# ProPrj__1_2024-08-31.net
KiCad netlist of a schematic drawn in EasyEDA Pro
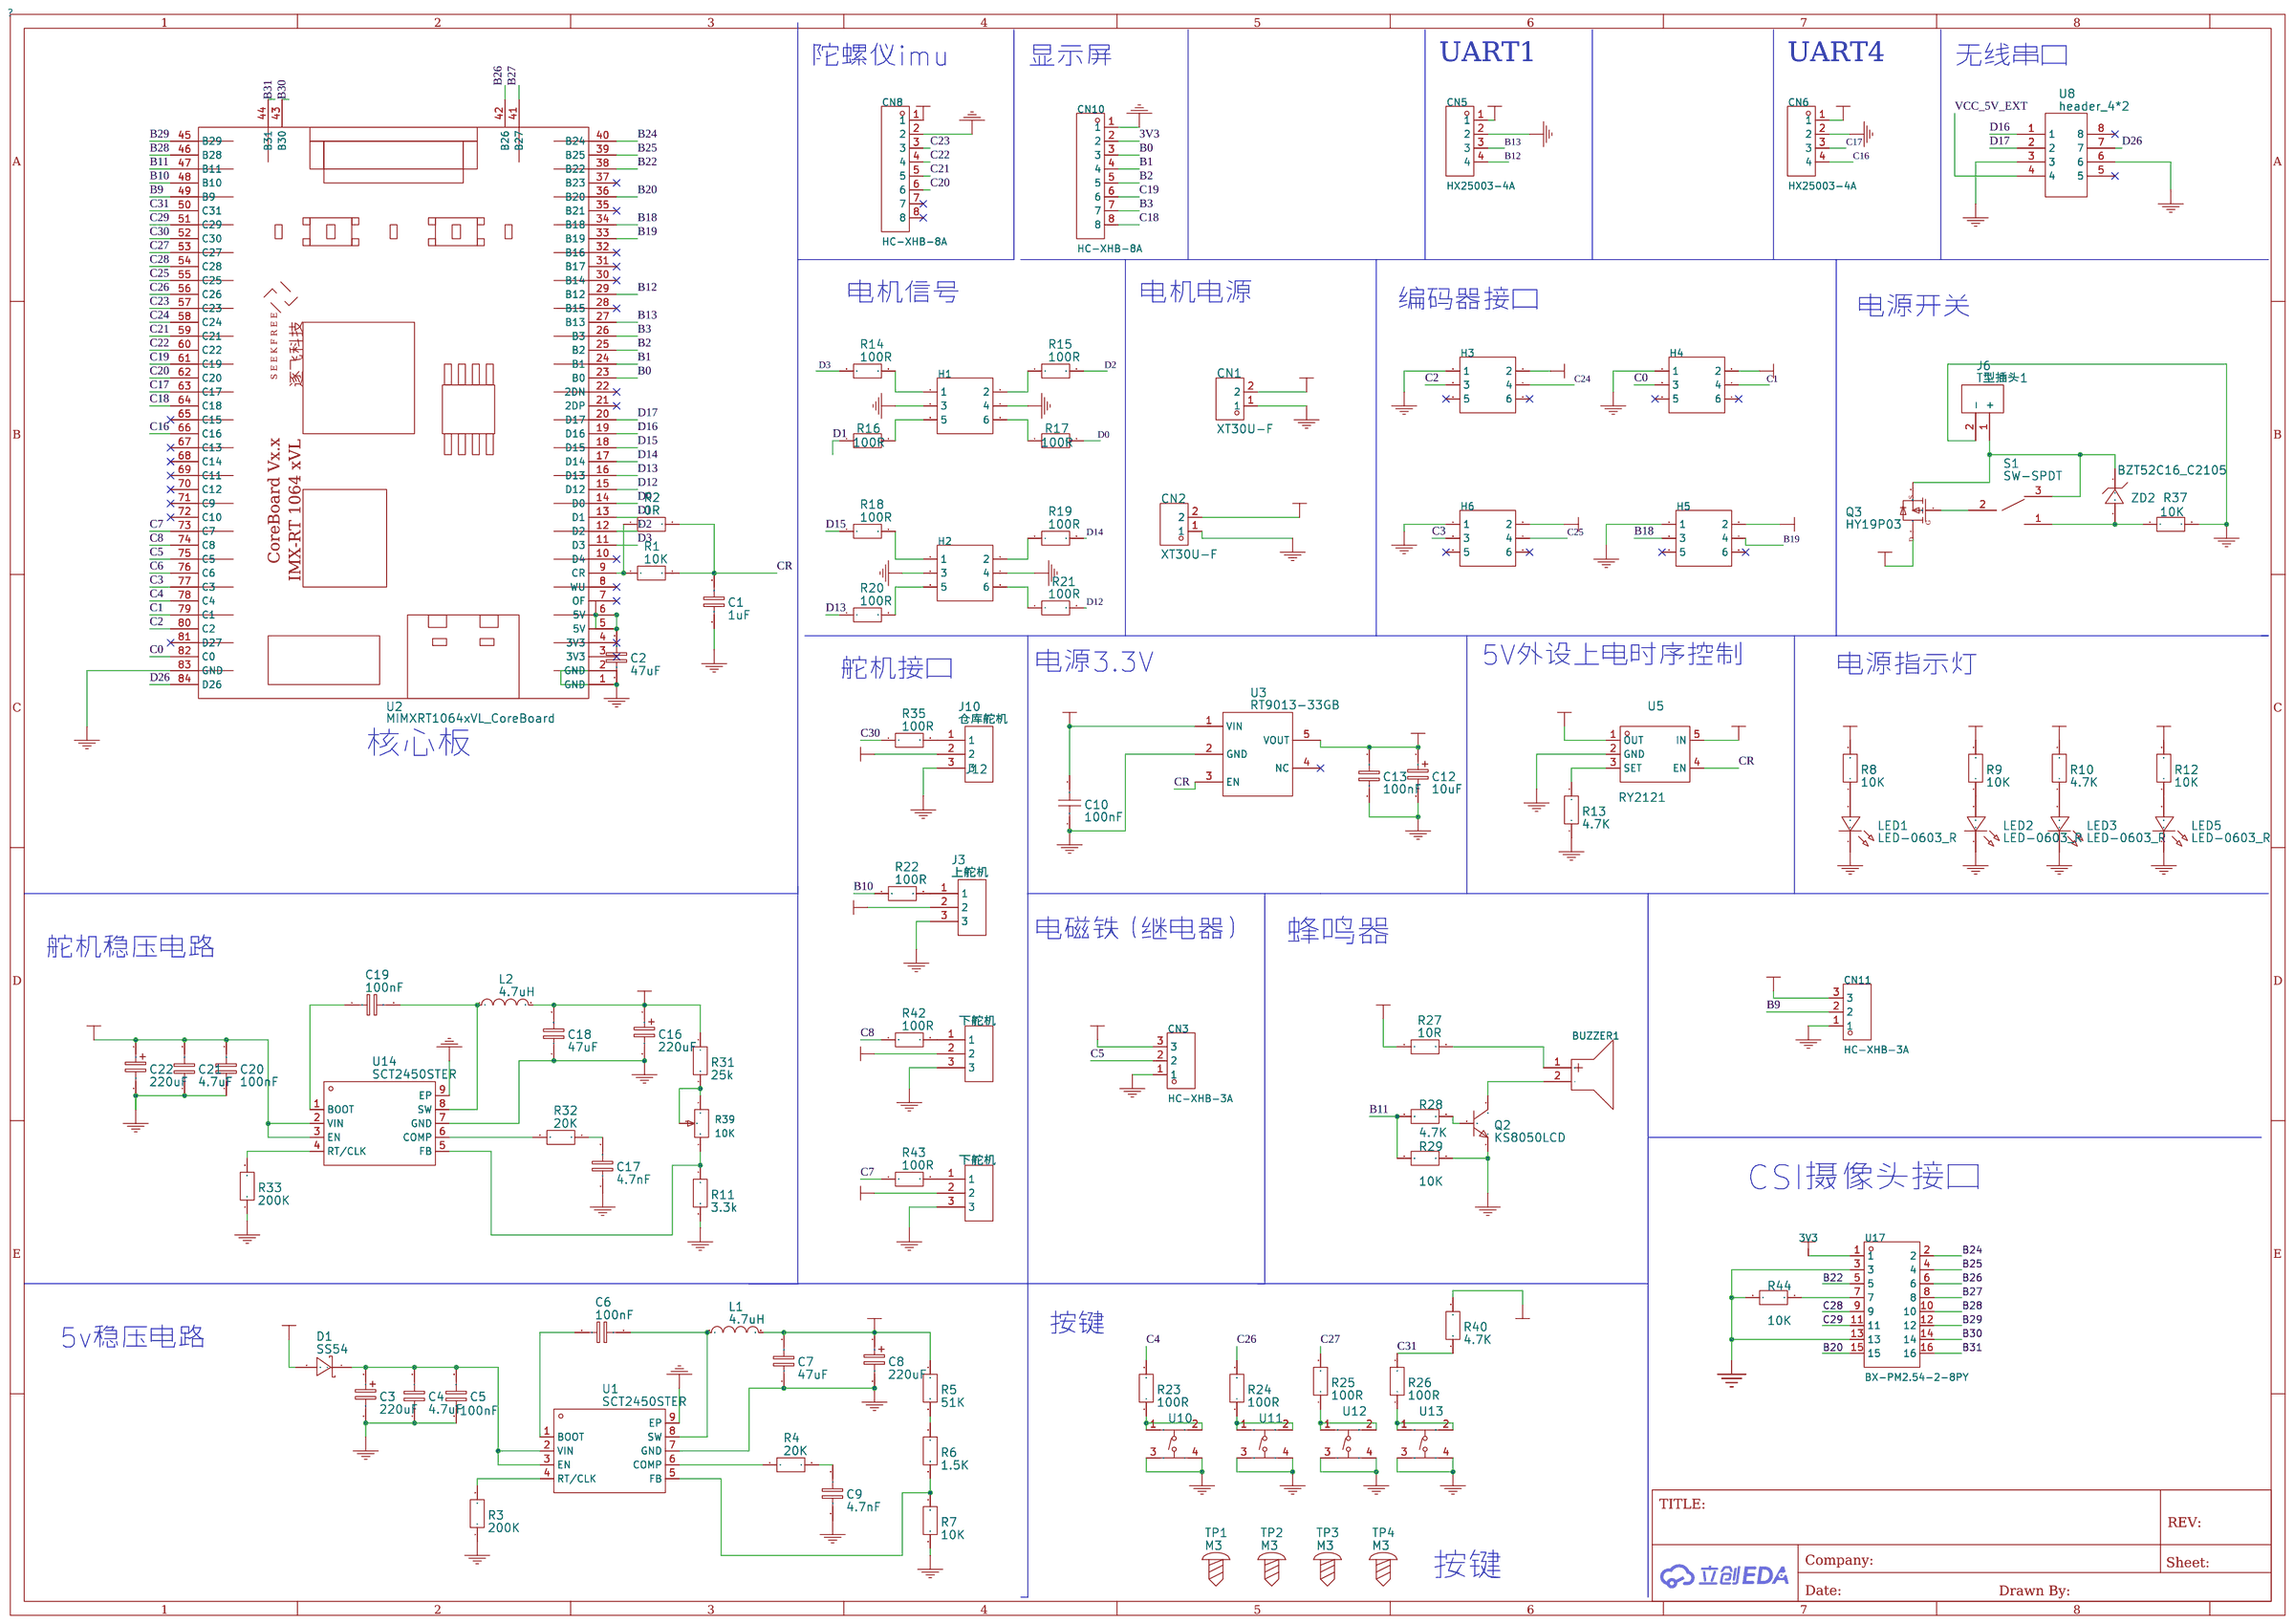
[diagram p0: schematic sheet]

(export (version "E")
  (design (tool "Eeschema 10.0.6"))
  (components
    (comp (ref "BUZZER1")
      (value "有源蜂鸣器直径9*5.5mm3V")
      (footprint "easyedapro:BUZ-TH_BD9.0-P5.00-D0.6-L-FD")
      (libsource (lib "easyedapro") (part "有源蜂鸣器直径9*5.5MM3V"))
    )
    (comp (ref "C1")
      (value "1uF")
      (footprint "easyedapro:C0603")
      (libsource (lib "easyedapro") (part "0.1u"))
    )
    (comp (ref "C2")
      (value "47uF")
      (footprint "easyedapro:C0603")
      (libsource (lib "easyedapro") (part "0.1u"))
    )
    (comp (ref "C3")
      (value "220uF")
      (footprint "easyedapro:贴片铝电解电容6.3*7.7")
      (libsource (lib "easyedapro") (part "220uF"))
    )
    (comp (ref "C4")
      (value "4.7uF")
      (footprint "easyedapro:C0603")
      (libsource (lib "easyedapro") (part "4.7uF"))
    )
    (comp (ref "C5")
      (value "100nF")
      (footprint "easyedapro:C0603")
      (libsource (lib "easyedapro") (part "100nF"))
    )
    (comp (ref "C6")
      (value "100nF")
      (footprint "easyedapro:C0603")
      (libsource (lib "easyedapro") (part "100nF"))
    )
    (comp (ref "C7")
      (value "47uF")
      (footprint "easyedapro:C0603")
      (libsource (lib "easyedapro") (part "47uF"))
    )
    (comp (ref "C8")
      (value "220uF")
      (footprint "easyedapro:贴片铝电解电容6.3*7.7")
      (libsource (lib "easyedapro") (part "220uF"))
    )
    (comp (ref "C9")
      (value "4.7nF")
      (footprint "easyedapro:C0603")
      (libsource (lib "easyedapro") (part "0.1u"))
    )
    (comp (ref "C10") (value "100nF") (footprint "easyedapro:C0603") (libsource (lib "") (part "100nF_1")))
    (comp (ref "C12")
      (value "10uF")
      (footprint "easyedapro:贴片铝电解电容6.3*7.7")
      (libsource (lib "easyedapro") (part "10uF"))
    )
    (comp (ref "C13")
      (value "100nF")
      (footprint "easyedapro:C0603")
      (libsource (lib "easyedapro") (part "100nF"))
    )
    (comp (ref "C16")
      (value "220uF")
      (footprint "easyedapro:贴片铝电解电容6.3*7.7")
      (libsource (lib "easyedapro") (part "220uF"))
    )
    (comp (ref "C17")
      (value "4.7nF")
      (footprint "easyedapro:C0603")
      (libsource (lib "easyedapro") (part "0.1u"))
    )
    (comp (ref "C18")
      (value "47uF")
      (footprint "easyedapro:C0603")
      (libsource (lib "easyedapro") (part "47uF"))
    )
    (comp (ref "C19")
      (value "100nF")
      (footprint "easyedapro:C0603")
      (libsource (lib "easyedapro") (part "100nF"))
    )
    (comp (ref "C20")
      (value "100nF")
      (footprint "easyedapro:C0603")
      (libsource (lib "easyedapro") (part "100nF"))
    )
    (comp (ref "C21")
      (value "4.7uF")
      (footprint "easyedapro:C0603")
      (libsource (lib "easyedapro") (part "4.7uF"))
    )
    (comp (ref "C22")
      (value "220uF")
      (footprint "easyedapro:贴片铝电解电容6.3*7.7")
      (libsource (lib "easyedapro") (part "220uF"))
    )
    (comp (ref "CN1")
      (value "XT30U-F")
      (footprint "easyedapro:CONN-TH_2P-P5.08_DIBO_DB128V-5.08")
      (fields (field (name "Manufacturer") "AMASS(艾迈斯)"))
      (libsource (lib "easyedapro") (part "DB128V-5.08-2P-GN-S"))
    )
    (comp (ref "CN2")
      (value "XT30U-F")
      (footprint "easyedapro:CONN-TH_2P-P5.08_DIBO_DB128V-5.08")
      (fields (field (name "Manufacturer") "AMASS(艾迈斯)"))
      (libsource (lib "easyedapro") (part "DB128V-5.08-2P-GN-S"))
    )
    (comp (ref "CN3")
      (value "HC-XHB-3A")
      (footprint "easyedapro:CONN-TH_3P-P2.50_HC-XHB-3A")
      (description "参考系列:-;间距:2.5mm;插针结构:1x3P;排数:1;每排PIN数:3;行距:-;公母:公型插针;安装方式:直插;额定电流:3A;工作温度范围:-25°C~+85°C;")
      (fields (field (name "Manufacturer") "HCTL(华灿天禄)"))
      (libsource (lib "easyedapro") (part "HC-XHB-3A"))
    )
    (comp (ref "CN5")
      (value "HX25003-4A")
      (footprint "easyedapro:CONN-TH_4P-P2.50_HX25003-4A")
      (description "参考系列:XH;间距:2.5mm;插针结构:1x4P;排数:1;每排PIN数:4;行距:-;公母:公型插针;安装方式:直插;额定电流:-;工作温度范围:-;")
      (fields (field (name "Manufacturer") "HX(红星)"))
      (libsource (lib "easyedapro") (part "HX25003-4A"))
    )
    (comp (ref "CN6")
      (value "HX25003-4A")
      (footprint "easyedapro:CONN-TH_4P-P2.50_HX25003-4A")
      (description "参考系列:XH;间距:2.5mm;插针结构:1x4P;排数:1;每排PIN数:4;行距:-;公母:公型插针;安装方式:直插;额定电流:-;工作温度范围:-;")
      (fields (field (name "Manufacturer") "HX(红星)"))
      (libsource (lib "easyedapro") (part "HX25003-4A"))
    )
    (comp (ref "CN8")
      (value "HC-XHB-8A")
      (footprint "easyedapro:CONN-TH_8P-P2.50_HCTL_HC-XHB-8A")
      (description "参考系列:-;间距:2.5mm;插针结构:1x8P;排数:1;每排PIN数:8;行距:-;公母:公型插针;安装方式:直插;额定电流:3A;工作温度范围:-25°C~+85°C;")
      (fields (field (name "Manufacturer") "HCTL(华灿天禄)"))
      (libsource (lib "easyedapro") (part "HC-XHB-8A"))
    )
    (comp (ref "CN10")
      (value "HC-XHB-8A")
      (footprint "easyedapro:CONN-TH_8P-P2.50_HCTL_HC-XHB-8A")
      (description "参考系列:-;间距:2.5mm;插针结构:1x8P;排数:1;每排PIN数:8;行距:-;公母:公型插针;安装方式:直插;额定电流:3A;工作温度范围:-25°C~+85°C;")
      (fields (field (name "Manufacturer") "HCTL(华灿天禄)"))
      (libsource (lib "easyedapro") (part "HC-XHB-8A"))
    )
    (comp (ref "CN11")
      (value "HC-XHB-3A")
      (footprint "easyedapro:CONN-TH_3P-P2.50_HC-XHB-3A")
      (description "参考系列:-;间距:2.5mm;插针结构:1x3P;排数:1;每排PIN数:3;行距:-;公母:公型插针;安装方式:直插;额定电流:3A;工作温度范围:-25°C~+85°C;")
      (fields (field (name "Manufacturer") "HCTL(华灿天禄)"))
      (libsource (lib "easyedapro") (part "HC-XHB-3A"))
    )
    (comp (ref "D1")
      (value "SS54")
      (footprint "easyedapro:SS54")
      (libsource (lib "easyedapro") (part "SS54"))
    )
    (comp (ref "H1")
      (value "~")
      (footprint "easyedapro:HDR-TH_6P-P2.54-V-F-R2-C3-S2.54")
      (libsource (lib "easyedapro") (part "HDR-F-2.54_2x3"))
    )
    (comp (ref "H2")
      (value "~")
      (footprint "easyedapro:HDR-TH_6P-P2.54-V-F-R2-C3-S2.54")
      (libsource (lib "easyedapro") (part "HDR-F-2.54_2x3"))
    )
    (comp (ref "H3")
      (value "~")
      (footprint "easyedapro:HDR-TH_6P-P2.54-V-F-R2-C3-S2.54")
      (libsource (lib "easyedapro") (part "HDR-F-2.54_2x3"))
    )
    (comp (ref "H4")
      (value "~")
      (footprint "easyedapro:HDR-TH_6P-P2.54-V-F-R2-C3-S2.54")
      (libsource (lib "easyedapro") (part "HDR-F-2.54_2x3"))
    )
    (comp (ref "H5")
      (value "~")
      (footprint "easyedapro:HDR-TH_6P-P2.54-V-F-R2-C3-S2.54")
      (libsource (lib "easyedapro") (part "HDR-F-2.54_2x3"))
    )
    (comp (ref "H6")
      (value "~")
      (footprint "easyedapro:HDR-TH_6P-P2.54-V-F-R2-C3-S2.54")
      (libsource (lib "easyedapro") (part "HDR-F-2.54_2x3"))
    )
    (comp (ref "J3")
      (value "上舵机")
      (footprint "easyedapro:2.54排针1X3")
      (libsource (lib "easyedapro") (part "舵机"))
    )
    (comp (ref "J6")
      (value "T型插头1")
      (footprint "easyedapro:T型插头")
      (libsource (lib "easyedapro") (part "T型插头1"))
    )
    (comp (ref "J10")
      (value "仓库舵机")
      (footprint "easyedapro:2.54排针1X3")
      (libsource (lib "easyedapro") (part "舵机"))
    )
    (comp (ref "J12")
      (value "下舵机")
      (footprint "easyedapro:2.54排针1X3")
      (libsource (lib "easyedapro") (part "舵机"))
    )
    (comp (ref "J13")
      (value "下舵机")
      (footprint "easyedapro:2.54排针1X3")
      (libsource (lib "easyedapro") (part "舵机"))
    )
    (comp (ref "L1")
      (value "4.7uH")
      (footprint "easyedapro:IND-SMD_L6.0-W6.0_SMNR6028")
      (fields
        (field (name "Manufacturer Part") "SMNR6028-680MT")
        (field (name "Manufacturer") "ShunXiang Connaught Elec")
      )
      (libsource (lib "easyedapro") (part "4.7uH"))
    )
    (comp (ref "L2")
      (value "4.7uH")
      (footprint "easyedapro:IND-SMD_L6.0-W6.0_SMNR6028")
      (fields
        (field (name "Manufacturer Part") "SMNR6028-680MT")
        (field (name "Manufacturer") "ShunXiang Connaught Elec")
      )
      (libsource (lib "easyedapro") (part "4.7uH"))
    )
    (comp (ref "LED1")
      (value "LED-0603_R")
      (footprint "easyedapro:LED0603_RED")
      (fields
        (field (name "Manufacturer Part") "19-217/R6C-AL1M2VY/3T")
        (field (name "Manufacturer") "EVERLIGHT(台湾亿光)")
      )
      (libsource (lib "easyedapro") (part "LED-0603_R"))
    )
    (comp (ref "LED2")
      (value "LED-0603_R")
      (footprint "easyedapro:LED0603_RED")
      (fields
        (field (name "Manufacturer Part") "19-217/R6C-AL1M2VY/3T")
        (field (name "Manufacturer") "EVERLIGHT(台湾亿光)")
      )
      (libsource (lib "easyedapro") (part "LED-0603_R"))
    )
    (comp (ref "LED3")
      (value "LED-0603_R")
      (footprint "easyedapro:LED0603_RED")
      (fields
        (field (name "Manufacturer Part") "19-217/R6C-AL1M2VY/3T")
        (field (name "Manufacturer") "EVERLIGHT(台湾亿光)")
      )
      (libsource (lib "easyedapro") (part "LED-0603_R"))
    )
    (comp (ref "LED5")
      (value "LED-0603_R")
      (footprint "easyedapro:LED0603_RED")
      (fields
        (field (name "Manufacturer Part") "19-217/R6C-AL1M2VY/3T")
        (field (name "Manufacturer") "EVERLIGHT(台湾亿光)")
      )
      (libsource (lib "easyedapro") (part "LED-0603_R"))
    )
    (comp (ref "Q2")
      (value "KS8050LCD")
      (footprint "easyedapro:SOT-23-3_L2.9-W1.3-P1.90-LS2.4-BR")
      (fields (field (name "Manufacturer") "Kodenshi AUK"))
      (libsource (lib "easyedapro") (part "KS8050LCD"))
    )
    (comp (ref "Q3")
      (value "HY19P03")
      (footprint "easyedapro:TO-252AA")
      (libsource (lib "easyedapro") (part "HY19P03"))
    )
    (comp (ref "R1") (value "10K") (footprint "easyedapro:R0603") (libsource (lib "easyedapro") (part "10k")))
    (comp (ref "R2") (value "0R") (footprint "easyedapro:R0603") (libsource (lib "easyedapro") (part "0R")))
    (comp (ref "R3")
      (value "200K")
      (footprint "easyedapro:R0603")
      (libsource (lib "easyedapro") (part "200K"))
    )
    (comp (ref "R4") (value "20K") (footprint "easyedapro:R0603") (libsource (lib "easyedapro") (part "1k")))
    (comp (ref "R5") (value "51K") (footprint "easyedapro:R0603") (libsource (lib "easyedapro") (part "51K")))
    (comp (ref "R6")
      (value "1.5K")
      (footprint "easyedapro:R0603")
      (libsource (lib "easyedapro") (part "1.5K"))
    )
    (comp (ref "R7") (value "10K") (footprint "easyedapro:R0603") (libsource (lib "easyedapro") (part "10K")))
    (comp (ref "R8") (value "10K") (footprint "easyedapro:R0603") (libsource (lib "easyedapro") (part "10K")))
    (comp (ref "R9") (value "10K") (footprint "easyedapro:R0603") (libsource (lib "easyedapro") (part "10K")))
    (comp (ref "R10")
      (value "4.7K")
      (footprint "easyedapro:R0603")
      (libsource (lib "easyedapro") (part "10K"))
    )
    (comp (ref "R11")
      (value "3.3k")
      (footprint "easyedapro:R0603")
      (libsource (lib "easyedapro") (part "10K"))
    )
    (comp (ref "R12")
      (value "10K")
      (footprint "easyedapro:R0603")
      (libsource (lib "easyedapro") (part "4.7K"))
    )
    (comp (ref "R13")
      (value "4.7K")
      (footprint "easyedapro:R0603")
      (libsource (lib "easyedapro") (part "4.7K"))
    )
    (comp (ref "R14")
      (value "100R")
      (footprint "easyedapro:R0603")
      (libsource (lib "easyedapro") (part "100R"))
    )
    (comp (ref "R15")
      (value "100R")
      (footprint "easyedapro:R0603")
      (libsource (lib "easyedapro") (part "100R"))
    )
    (comp (ref "R16")
      (value "100R")
      (footprint "easyedapro:R0603")
      (libsource (lib "easyedapro") (part "100R"))
    )
    (comp (ref "R17")
      (value "100R")
      (footprint "easyedapro:R0603")
      (libsource (lib "easyedapro") (part "100R"))
    )
    (comp (ref "R18")
      (value "100R")
      (footprint "easyedapro:R0603")
      (libsource (lib "easyedapro") (part "100R"))
    )
    (comp (ref "R19")
      (value "100R")
      (footprint "easyedapro:R0603")
      (libsource (lib "easyedapro") (part "100R"))
    )
    (comp (ref "R20")
      (value "100R")
      (footprint "easyedapro:R0603")
      (libsource (lib "easyedapro") (part "100R"))
    )
    (comp (ref "R21")
      (value "100R")
      (footprint "easyedapro:R0603")
      (libsource (lib "easyedapro") (part "100R"))
    )
    (comp (ref "R22")
      (value "100R")
      (footprint "easyedapro:R0603")
      (libsource (lib "easyedapro") (part "1k"))
    )
    (comp (ref "R23")
      (value "100R")
      (footprint "easyedapro:R0603")
      (libsource (lib "easyedapro") (part "100R"))
    )
    (comp (ref "R24")
      (value "100R")
      (footprint "easyedapro:R0603")
      (libsource (lib "easyedapro") (part "100R"))
    )
    (comp (ref "R25")
      (value "100R")
      (footprint "easyedapro:R0603")
      (libsource (lib "easyedapro") (part "100R"))
    )
    (comp (ref "R26")
      (value "100R")
      (footprint "easyedapro:R0603")
      (libsource (lib "easyedapro") (part "100R"))
    )
    (comp (ref "R27") (value "10R") (footprint "easyedapro:R0603") (libsource (lib "easyedapro") (part "1k")))
    (comp (ref "R28")
      (value "4.7K")
      (footprint "easyedapro:R0603")
      (libsource (lib "easyedapro") (part "1k"))
    )
    (comp (ref "R29") (value "10K") (footprint "easyedapro:R0603") (libsource (lib "easyedapro") (part "1k")))
    (comp (ref "R31")
      (value "25k")
      (footprint "easyedapro:R0603")
      (libsource (lib "easyedapro") (part "51K"))
    )
    (comp (ref "R32") (value "20K") (footprint "easyedapro:R0603") (libsource (lib "easyedapro") (part "1k")))
    (comp (ref "R33")
      (value "200K")
      (footprint "easyedapro:R0603")
      (libsource (lib "easyedapro") (part "200K"))
    )
    (comp (ref "R35")
      (value "100R")
      (footprint "easyedapro:R0603")
      (libsource (lib "easyedapro") (part "1k"))
    )
    (comp (ref "R37")
      (value "10K")
      (footprint "easyedapro:R0603")
      (libsource (lib "easyedapro") (part "10K"))
    )
    (comp (ref "R39")
      (value "10K")
      (footprint "easyedapro:RES-ADJ-TH_3296W")
      (description "阻值:10kΩ;精度:±10%;")
      (fields (field (name "Manufacturer Part") "3296W-1-103LF") (field (name "Manufacturer") "BOURNS"))
      (libsource (lib "easyedapro") (part "3296W-1-103LF"))
    )
    (comp (ref "R40")
      (value "4.7K")
      (footprint "easyedapro:R0603")
      (libsource (lib "easyedapro") (part "100R"))
    )
    (comp (ref "R42")
      (value "100R")
      (footprint "easyedapro:R0603")
      (libsource (lib "easyedapro") (part "1k"))
    )
    (comp (ref "R43")
      (value "100R")
      (footprint "easyedapro:R0603")
      (libsource (lib "easyedapro") (part "1k"))
    )
    (comp (ref "R44") (value "10K") (footprint "easyedapro:R0603") (libsource (lib "easyedapro") (part "1k")))
    (comp (ref "S1")
      (value "SW-SPDT")
      (footprint "easyedapro:SS12D10")
      (fields (field (name "Publisher") "Altium Limited"))
      (libsource (lib "easyedapro") (part "SW-SPDT"))
    )
    (comp (ref "TP1") (value "M3") (footprint "easyedapro:M3") (libsource (lib "easyedapro") (part "M3")))
    (comp (ref "TP2") (value "M3") (footprint "easyedapro:M3") (libsource (lib "easyedapro") (part "M3")))
    (comp (ref "TP3") (value "M3") (footprint "easyedapro:M3") (libsource (lib "easyedapro") (part "M3")))
    (comp (ref "TP4") (value "M3") (footprint "easyedapro:M3") (libsource (lib "easyedapro") (part "M3")))
    (comp (ref "U1")
      (value "SCT2450STER")
      (footprint "easyedapro:ESOP-8_L4.9-W3.9-P1.27-LS6.0-BL-EP")
      (fields (field (name "Manufacturer") "SCT"))
      (libsource (lib "easyedapro") (part "SCT2450STER"))
    )
    (comp (ref "U2")
      (value "MIMXRT1064xVL_CoreBoard")
      (footprint "easyedapro:MIMXRT1064XVL_COREBOARD")
      (libsource (lib "easyedapro") (part "MIMXRT1064xVL_CoreBoard"))
    )
    (comp (ref "U3")
      (value "RT9013-33GB")
      (footprint "easyedapro:SOT-23-5_L3.0-W1.7-P0.95-LS2.8-BR")
      (fields (field (name "Manufacturer") "RICHTEK"))
      (libsource (lib "easyedapro") (part "RT9013-33GB"))
    )
    (comp (ref "U5")
      (value "RY2121")
      (footprint "easyedapro:SOT-23-5_L3.0-W1.6-P0.95-LS2.8-BL")
      (fields (field (name "Manufacturer") "RYCHiP(蕊源)"))
      (libsource (lib "easyedapro") (part "RY2121"))
    )
    (comp (ref "U8")
      (value "header_4*2")
      (footprint "easyedapro:HEADER_4*2")
      (libsource (lib "easyedapro") (part "header_4*2"))
    )
    (comp (ref "U10")
      (value "贴片按键4*4*3.5M")
      (footprint "easyedapro:KEY-SMD_4P-L5.1-W5.1-P3.70-LS6.5")
      (fields (field (name "Manufacturer Part") "贴片按键4*4*3.5m"))
      (libsource (lib "easyedapro") (part "贴片按键4*4*3.5M"))
    )
    (comp (ref "U11")
      (value "贴片按键4*4*3.5M")
      (footprint "easyedapro:KEY-SMD_4P-L5.1-W5.1-P3.70-LS6.5")
      (fields (field (name "Manufacturer Part") "贴片按键4*4*3.5m"))
      (libsource (lib "easyedapro") (part "贴片按键4*4*3.5M"))
    )
    (comp (ref "U12")
      (value "贴片按键4*4*3.5M")
      (footprint "easyedapro:KEY-SMD_4P-L5.1-W5.1-P3.70-LS6.5")
      (fields (field (name "Manufacturer Part") "贴片按键4*4*3.5m"))
      (libsource (lib "easyedapro") (part "贴片按键4*4*3.5M"))
    )
    (comp (ref "U13")
      (value "贴片按键4*4*3.5M")
      (footprint "easyedapro:KEY-SMD_4P-L5.1-W5.1-P3.70-LS6.5")
      (fields (field (name "Manufacturer Part") "贴片按键4*4*3.5m"))
      (libsource (lib "easyedapro") (part "贴片按键4*4*3.5M"))
    )
    (comp (ref "U14")
      (value "SCT2450STER")
      (footprint "easyedapro:ESOP-8_L4.9-W3.9-P1.27-LS6.0-BL-EP")
      (fields (field (name "Manufacturer") "SCT"))
      (libsource (lib "easyedapro") (part "SCT2450STER"))
    )
    (comp (ref "U17")
      (value "BX-PM2.54-2-8PY")
      (footprint "easyedapro:HDR-TH_16P-P2.54-V-F-R2-C8-S2.54-1")
      (fields (field (name "Manufacturer") "Bossie(博锡)"))
      (libsource (lib "easyedapro") (part "BX-PM2.54-2-8PY"))
    )
    (comp (ref "ZD2")
      (value "BZT52C16_C2105")
      (footprint "easyedapro:SOD-123_L2.8-W1.8-LS3.7-RD")
      (fields (field (name "Manufacturer Part") "BZT52C16") (field (name "Manufacturer") "CJ"))
      (libsource (lib "easyedapro") (part "BZT52C16_C2105"))
    )
  )
  (nets
    (net (code "1") (name "/B0") (class "Default")
      (node (ref "CN10") (pin "3") (pinfunction "3_3") (pintype "input"))
      (node (ref "U2") (pin "23") (pinfunction "B0_23") (pintype "input"))
    )
    (net (code "2") (name "/B1") (class "Default")
      (node (ref "CN10") (pin "4") (pinfunction "4_4") (pintype "input"))
      (node (ref "U2") (pin "24") (pinfunction "B1_24") (pintype "input"))
    )
    (net (code "3") (name "/B2") (class "Default")
      (node (ref "CN10") (pin "5") (pinfunction "5_5") (pintype "input"))
      (node (ref "U2") (pin "25") (pinfunction "B2_25") (pintype "input"))
    )
    (net (code "4") (name "/B3") (class "Default")
      (node (ref "CN10") (pin "7") (pinfunction "7_7") (pintype "input"))
      (node (ref "U2") (pin "26") (pinfunction "B3_26") (pintype "input"))
    )
    (net (code "5") (name "/B9") (class "Default")
      (node (ref "CN11") (pin "2") (pinfunction "2_2") (pintype "input"))
      (node (ref "U2") (pin "49") (pinfunction "B9_49") (pintype "input"))
    )
    (net (code "6") (name "/B10") (class "Default")
      (node (ref "R22") (pin "1") (pinfunction "1_1") (pintype "input"))
      (node (ref "U2") (pin "48") (pinfunction "B10_48") (pintype "input"))
    )
    (net (code "7") (name "/B11") (class "Default")
      (node (ref "R28") (pin "1") (pinfunction "1_1") (pintype "input"))
      (node (ref "R29") (pin "1") (pinfunction "1_1") (pintype "input"))
      (node (ref "U2") (pin "47") (pinfunction "B11_47") (pintype "input"))
    )
    (net (code "8") (name "/B12") (class "Default")
      (node (ref "CN5") (pin "4") (pinfunction "4_4") (pintype "input"))
      (node (ref "U2") (pin "29") (pinfunction "B12_29") (pintype "input"))
    )
    (net (code "9") (name "/B13") (class "Default")
      (node (ref "CN5") (pin "3") (pinfunction "3_3") (pintype "input"))
      (node (ref "U2") (pin "27") (pinfunction "B13_27") (pintype "input"))
    )
    (net (code "10") (name "/B18") (class "Default")
      (node (ref "H5") (pin "3") (pinfunction "3_3") (pintype "input"))
      (node (ref "U2") (pin "34") (pinfunction "B18_34") (pintype "input"))
    )
    (net (code "11") (name "/B19") (class "Default")
      (node (ref "H5") (pin "4") (pinfunction "4_4") (pintype "input"))
      (node (ref "U2") (pin "33") (pinfunction "B19_33") (pintype "input"))
    )
    (net (code "12") (name "/B20") (class "Default")
      (node (ref "U17") (pin "15") (pinfunction "15_15") (pintype "unspecified"))
      (node (ref "U2") (pin "36") (pinfunction "B20_36") (pintype "input"))
    )
    (net (code "13") (name "/B22") (class "Default")
      (node (ref "U17") (pin "5") (pinfunction "5_5") (pintype "unspecified"))
      (node (ref "U2") (pin "38") (pinfunction "B22_38") (pintype "input"))
    )
    (net (code "14") (name "/B24") (class "Default")
      (node (ref "U17") (pin "2") (pinfunction "2_2") (pintype "unspecified"))
      (node (ref "U2") (pin "40") (pinfunction "B24_40") (pintype "input"))
    )
    (net (code "15") (name "/B25") (class "Default")
      (node (ref "U17") (pin "4") (pinfunction "4_4") (pintype "unspecified"))
      (node (ref "U2") (pin "39") (pinfunction "B25_39") (pintype "input"))
    )
    (net (code "16") (name "/B26") (class "Default")
      (node (ref "U17") (pin "6") (pinfunction "6_6") (pintype "unspecified"))
      (node (ref "U2") (pin "42") (pinfunction "B26_42") (pintype "input"))
    )
    (net (code "17") (name "/B27") (class "Default")
      (node (ref "U17") (pin "8") (pinfunction "8_8") (pintype "unspecified"))
      (node (ref "U2") (pin "41") (pinfunction "B27_41") (pintype "input"))
    )
    (net (code "18") (name "/B28") (class "Default")
      (node (ref "U17") (pin "10") (pinfunction "10_10") (pintype "unspecified"))
      (node (ref "U2") (pin "46") (pinfunction "B28_46") (pintype "input"))
    )
    (net (code "19") (name "/B29") (class "Default")
      (node (ref "U17") (pin "12") (pinfunction "12_12") (pintype "unspecified"))
      (node (ref "U2") (pin "45") (pinfunction "B29_45") (pintype "input"))
    )
    (net (code "20") (name "/B30") (class "Default")
      (node (ref "U17") (pin "14") (pinfunction "14_14") (pintype "unspecified"))
      (node (ref "U2") (pin "43") (pinfunction "B30_43") (pintype "input"))
    )
    (net (code "21") (name "/B31") (class "Default")
      (node (ref "U17") (pin "16") (pinfunction "16_16") (pintype "unspecified"))
      (node (ref "U2") (pin "44") (pinfunction "B31_44") (pintype "input"))
    )
    (net (code "22") (name "/C0") (class "Default")
      (node (ref "H4") (pin "3") (pinfunction "3_3") (pintype "input"))
      (node (ref "U2") (pin "82") (pinfunction "C0_82") (pintype "input"))
    )
    (net (code "23") (name "/C1") (class "Default")
      (node (ref "H4") (pin "4") (pinfunction "4_4") (pintype "input"))
      (node (ref "U2") (pin "79") (pinfunction "C1_79") (pintype "input"))
    )
    (net (code "24") (name "/C2") (class "Default")
      (node (ref "H3") (pin "3") (pinfunction "3_3") (pintype "input"))
      (node (ref "U2") (pin "80") (pinfunction "C2_80") (pintype "input"))
    )
    (net (code "25") (name "/C3") (class "Default")
      (node (ref "H6") (pin "3") (pinfunction "3_3") (pintype "input"))
      (node (ref "U2") (pin "77") (pinfunction "C3_77") (pintype "input"))
    )
    (net (code "26") (name "/C4") (class "Default")
      (node (ref "R23") (pin "2") (pinfunction "2_2") (pintype "input"))
      (node (ref "U2") (pin "78") (pinfunction "C4_78") (pintype "input"))
    )
    (net (code "27") (name "/C5") (class "Default")
      (node (ref "CN3") (pin "2") (pinfunction "2_2") (pintype "input"))
      (node (ref "U2") (pin "75") (pinfunction "C5_75") (pintype "input"))
    )
    (net (code "28") (name "/C6") (class "Default")
      (node (ref "U2") (pin "76") (pinfunction "C6_76") (pintype "input"))
    )
    (net (code "29") (name "/C7") (class "Default")
      (node (ref "R43") (pin "1") (pinfunction "1_1") (pintype "input"))
      (node (ref "U2") (pin "73") (pinfunction "C7_73") (pintype "input"))
    )
    (net (code "30") (name "/C8") (class "Default")
      (node (ref "R42") (pin "1") (pinfunction "1_1") (pintype "input"))
      (node (ref "U2") (pin "74") (pinfunction "C8_74") (pintype "input"))
    )
    (net (code "31") (name "/C16") (class "Default")
      (node (ref "CN6") (pin "4") (pinfunction "4_4") (pintype "input"))
      (node (ref "U2") (pin "66") (pinfunction "C16_66") (pintype "input"))
    )
    (net (code "32") (name "/C17") (class "Default")
      (node (ref "CN6") (pin "3") (pinfunction "3_3") (pintype "input"))
      (node (ref "U2") (pin "63") (pinfunction "C17_63") (pintype "input"))
    )
    (net (code "33") (name "/C18") (class "Default")
      (node (ref "CN10") (pin "8") (pinfunction "8_8") (pintype "input"))
      (node (ref "U2") (pin "64") (pinfunction "C18_64") (pintype "input"))
    )
    (net (code "34") (name "/C19") (class "Default")
      (node (ref "CN10") (pin "6") (pinfunction "6_6") (pintype "input"))
      (node (ref "U2") (pin "61") (pinfunction "C19_61") (pintype "input"))
    )
    (net (code "35") (name "/C20") (class "Default")
      (node (ref "CN8") (pin "6") (pinfunction "6_6") (pintype "input"))
      (node (ref "U2") (pin "62") (pinfunction "C20_62") (pintype "input"))
    )
    (net (code "36") (name "/C21") (class "Default")
      (node (ref "CN8") (pin "5") (pinfunction "5_5") (pintype "input"))
      (node (ref "U2") (pin "59") (pinfunction "C21_59") (pintype "input"))
    )
    (net (code "37") (name "/C22") (class "Default")
      (node (ref "CN8") (pin "4") (pinfunction "4_4") (pintype "input"))
      (node (ref "U2") (pin "60") (pinfunction "C22_60") (pintype "input"))
    )
    (net (code "38") (name "/C23") (class "Default")
      (node (ref "CN8") (pin "3") (pinfunction "3_3") (pintype "input"))
      (node (ref "U2") (pin "57") (pinfunction "C23_57") (pintype "input"))
    )
    (net (code "39") (name "/C24") (class "Default")
      (node (ref "H3") (pin "4") (pinfunction "4_4") (pintype "input"))
      (node (ref "U2") (pin "58") (pinfunction "C24_58") (pintype "input"))
    )
    (net (code "40") (name "/C25") (class "Default")
      (node (ref "H6") (pin "4") (pinfunction "4_4") (pintype "input"))
      (node (ref "U2") (pin "55") (pinfunction "C25_55") (pintype "input"))
    )
    (net (code "41") (name "/C26") (class "Default")
      (node (ref "R24") (pin "2") (pinfunction "2_2") (pintype "input"))
      (node (ref "U2") (pin "56") (pinfunction "C26_56") (pintype "input"))
    )
    (net (code "42") (name "/C27") (class "Default")
      (node (ref "R25") (pin "2") (pinfunction "2_2") (pintype "input"))
      (node (ref "U2") (pin "53") (pinfunction "C27_53") (pintype "input"))
    )
    (net (code "43") (name "/C28") (class "Default")
      (node (ref "U17") (pin "9") (pinfunction "9_9") (pintype "unspecified"))
      (node (ref "U2") (pin "54") (pinfunction "C28_54") (pintype "input"))
    )
    (net (code "44") (name "/C29") (class "Default")
      (node (ref "U17") (pin "11") (pinfunction "11_11") (pintype "unspecified"))
      (node (ref "U2") (pin "51") (pinfunction "C29_51") (pintype "input"))
    )
    (net (code "45") (name "/C30") (class "Default")
      (node (ref "R35") (pin "1") (pinfunction "1_1") (pintype "input"))
      (node (ref "U2") (pin "52") (pinfunction "C30_52") (pintype "input"))
    )
    (net (code "46") (name "/C31") (class "Default")
      (node (ref "R26") (pin "2") (pinfunction "2_2") (pintype "input"))
      (node (ref "R40") (pin "1") (pinfunction "1_1") (pintype "input"))
      (node (ref "U2") (pin "50") (pinfunction "C31_50") (pintype "input"))
    )
    (net (code "47") (name "/CR") (class "Default")
      (node (ref "C1") (pin "2") (pinfunction "2_2") (pintype "input"))
      (node (ref "R1") (pin "2") (pinfunction "2_2") (pintype "input"))
      (node (ref "R2") (pin "2") (pinfunction "2_2") (pintype "input"))
      (node (ref "U3") (pin "3") (pinfunction "EN_3") (pintype "input"))
      (node (ref "U5") (pin "4") (pinfunction "EN_4") (pintype "input"))
    )
    (net (code "48") (name "/D0") (class "Default")
      (node (ref "R17") (pin "2") (pinfunction "2_2") (pintype "input"))
      (node (ref "U2") (pin "14") (pinfunction "D0_14") (pintype "input"))
    )
    (net (code "49") (name "/D1") (class "Default")
      (node (ref "R16") (pin "1") (pinfunction "1_1") (pintype "input"))
      (node (ref "U2") (pin "13") (pinfunction "D1_13") (pintype "input"))
    )
    (net (code "50") (name "/D2") (class "Default")
      (node (ref "R15") (pin "2") (pinfunction "2_2") (pintype "input"))
      (node (ref "U2") (pin "12") (pinfunction "D2_12") (pintype "input"))
    )
    (net (code "51") (name "/D3") (class "Default")
      (node (ref "R14") (pin "1") (pinfunction "1_1") (pintype "input"))
      (node (ref "U2") (pin "11") (pinfunction "D3_11") (pintype "input"))
    )
    (net (code "52") (name "/D12") (class "Default")
      (node (ref "R21") (pin "2") (pinfunction "2_2") (pintype "input"))
      (node (ref "U2") (pin "15") (pinfunction "D12_15") (pintype "input"))
    )
    (net (code "53") (name "/D13") (class "Default")
      (node (ref "R20") (pin "1") (pinfunction "1_1") (pintype "input"))
      (node (ref "U2") (pin "16") (pinfunction "D13_16") (pintype "input"))
    )
    (net (code "54") (name "/D14") (class "Default")
      (node (ref "R19") (pin "2") (pinfunction "2_2") (pintype "input"))
      (node (ref "U2") (pin "17") (pinfunction "D14_17") (pintype "input"))
    )
    (net (code "55") (name "/D15") (class "Default")
      (node (ref "R18") (pin "1") (pinfunction "1_1") (pintype "input"))
      (node (ref "U2") (pin "18") (pinfunction "D15_18") (pintype "input"))
    )
    (net (code "56") (name "/D16") (class "Default")
      (node (ref "U2") (pin "19") (pinfunction "D16_19") (pintype "input"))
      (node (ref "U8") (pin "1") (pinfunction "1_1") (pintype "input"))
    )
    (net (code "57") (name "/D17") (class "Default")
      (node (ref "U2") (pin "20") (pinfunction "D17_20") (pintype "input"))
      (node (ref "U8") (pin "2") (pinfunction "2_2") (pintype "input"))
    )
    (net (code "58") (name "/D26") (class "Default")
      (node (ref "U2") (pin "84") (pinfunction "D26_84") (pintype "input"))
      (node (ref "U8") (pin "7") (pinfunction "7_7") (pintype "input"))
    )
    (net (code "59") (name "3V3") (class "Default")
      (node (ref "C12") (pin "1") (pinfunction "1_1") (pintype "input"))
      (node (ref "C13") (pin "2") (pinfunction "2_2") (pintype "input"))
      (node (ref "CN10") (pin "2") (pinfunction "2_2") (pintype "input"))
      (node (ref "CN8") (pin "1") (pinfunction "1_1") (pintype "input"))
      (node (ref "H3") (pin "2") (pinfunction "2_2") (pintype "input"))
      (node (ref "H4") (pin "2") (pinfunction "2_2") (pintype "input"))
      (node (ref "H5") (pin "2") (pinfunction "2_2") (pintype "input"))
      (node (ref "H6") (pin "2") (pinfunction "2_2") (pintype "input"))
      (node (ref "R10") (pin "2") (pinfunction "2_2") (pintype "input"))
      (node (ref "R27") (pin "1") (pinfunction "1_1") (pintype "input"))
      (node (ref "R40") (pin "2") (pinfunction "2_2") (pintype "input"))
      (node (ref "U17") (pin "1") (pinfunction "1_1") (pintype "unspecified"))
      (node (ref "U3") (pin "5") (pinfunction "VOUT_5") (pintype "input"))
    )
    (net (code "60") (name "GND") (class "Default")
      (node (ref "C1") (pin "1") (pinfunction "1_1") (pintype "input"))
      (node (ref "C10") (pin "1") (pinfunction "1_1") (pintype "input"))
      (node (ref "C12") (pin "2") (pinfunction "2_2") (pintype "input"))
      (node (ref "C13") (pin "1") (pinfunction "1_1") (pintype "input"))
      (node (ref "C16") (pin "2") (pinfunction "2_2") (pintype "input"))
      (node (ref "C17") (pin "1") (pinfunction "1_1") (pintype "input"))
      (node (ref "C18") (pin "1") (pinfunction "1_1") (pintype "input"))
      (node (ref "C2") (pin "1") (pinfunction "1_1") (pintype "input"))
      (node (ref "C20") (pin "1") (pinfunction "1_1") (pintype "input"))
      (node (ref "C21") (pin "1") (pinfunction "1_1") (pintype "input"))
      (node (ref "C22") (pin "2") (pinfunction "2_2") (pintype "input"))
      (node (ref "C3") (pin "2") (pinfunction "2_2") (pintype "input"))
      (node (ref "C4") (pin "1") (pinfunction "1_1") (pintype "input"))
      (node (ref "C5") (pin "1") (pinfunction "1_1") (pintype "input"))
      (node (ref "C7") (pin "1") (pinfunction "1_1") (pintype "input"))
      (node (ref "C8") (pin "2") (pinfunction "2_2") (pintype "input"))
      (node (ref "C9") (pin "1") (pinfunction "1_1") (pintype "input"))
      (node (ref "CN1") (pin "1") (pinfunction "1_1") (pintype "input"))
      (node (ref "CN10") (pin "1") (pinfunction "1_1") (pintype "input"))
      (node (ref "CN11") (pin "1") (pinfunction "1_1") (pintype "input"))
      (node (ref "CN2") (pin "1") (pinfunction "1_1") (pintype "input"))
      (node (ref "CN3") (pin "1") (pinfunction "1_1") (pintype "input"))
      (node (ref "CN5") (pin "2") (pinfunction "2_2") (pintype "input"))
      (node (ref "CN6") (pin "2") (pinfunction "2_2") (pintype "input"))
      (node (ref "CN8") (pin "2") (pinfunction "2_2") (pintype "input"))
      (node (ref "H1") (pin "3") (pinfunction "3_3") (pintype "input"))
      (node (ref "H1") (pin "4") (pinfunction "4_4") (pintype "input"))
      (node (ref "H2") (pin "3") (pinfunction "3_3") (pintype "input"))
      (node (ref "H2") (pin "4") (pinfunction "4_4") (pintype "input"))
      (node (ref "H3") (pin "1") (pinfunction "1_1") (pintype "input"))
      (node (ref "H4") (pin "1") (pinfunction "1_1") (pintype "input"))
      (node (ref "H5") (pin "1") (pinfunction "1_1") (pintype "input"))
      (node (ref "H6") (pin "1") (pinfunction "1_1") (pintype "input"))
      (node (ref "J10") (pin "3") (pinfunction "3_3") (pintype "input"))
      (node (ref "J12") (pin "3") (pinfunction "3_3") (pintype "input"))
      (node (ref "J13") (pin "3") (pinfunction "3_3") (pintype "input"))
      (node (ref "J3") (pin "3") (pinfunction "3_3") (pintype "input"))
      (node (ref "J6") (pin "2") (pinfunction "-_2") (pintype "input"))
      (node (ref "LED1") (pin "2") (pinfunction "2_2") (pintype "input"))
      (node (ref "LED2") (pin "2") (pinfunction "2_2") (pintype "input"))
      (node (ref "LED3") (pin "2") (pinfunction "2_2") (pintype "input"))
      (node (ref "LED5") (pin "2") (pinfunction "2_2") (pintype "input"))
      (node (ref "Q2") (pin "2") (pinfunction "E_2") (pintype "input"))
      (node (ref "R11") (pin "2") (pinfunction "2_2") (pintype "input"))
      (node (ref "R13") (pin "1") (pinfunction "1_1") (pintype "input"))
      (node (ref "R29") (pin "2") (pinfunction "2_2") (pintype "input"))
      (node (ref "R3") (pin "1") (pinfunction "1_1") (pintype "input"))
      (node (ref "R33") (pin "1") (pinfunction "1_1") (pintype "input"))
      (node (ref "R37") (pin "2") (pinfunction "2_2") (pintype "input"))
      (node (ref "R44") (pin "1") (pinfunction "1_1") (pintype "input"))
      (node (ref "R7") (pin "2") (pinfunction "2_2") (pintype "input"))
      (node (ref "U1") (pin "7") (pinfunction "GND_7") (pintype "input"))
      (node (ref "U1") (pin "9") (pinfunction "EP_9") (pintype "input"))
      (node (ref "U10") (pin "3") (pinfunction "3_3") (pintype "input"))
      (node (ref "U10") (pin "4") (pinfunction "4_4") (pintype "input"))
      (node (ref "U11") (pin "3") (pinfunction "3_3") (pintype "input"))
      (node (ref "U11") (pin "4") (pinfunction "4_4") (pintype "input"))
      (node (ref "U12") (pin "3") (pinfunction "3_3") (pintype "input"))
      (node (ref "U12") (pin "4") (pinfunction "4_4") (pintype "input"))
      (node (ref "U13") (pin "3") (pinfunction "3_3") (pintype "input"))
      (node (ref "U13") (pin "4") (pinfunction "4_4") (pintype "input"))
      (node (ref "U14") (pin "7") (pinfunction "GND_7") (pintype "input"))
      (node (ref "U14") (pin "9") (pinfunction "EP_9") (pintype "input"))
      (node (ref "U17") (pin "13") (pinfunction "13_13") (pintype "unspecified"))
      (node (ref "U17") (pin "3") (pinfunction "3_3") (pintype "unspecified"))
      (node (ref "U2") (pin "1") (pinfunction "GND_1") (pintype "input"))
      (node (ref "U2") (pin "2") (pinfunction "GND_2") (pintype "input"))
      (node (ref "U2") (pin "83") (pinfunction "GND_83") (pintype "input"))
      (node (ref "U3") (pin "2") (pinfunction "GND_2") (pintype "input"))
      (node (ref "U5") (pin "2") (pinfunction "GND_2") (pintype "input"))
      (node (ref "U8") (pin "3") (pinfunction "3_3") (pintype "input"))
      (node (ref "U8") (pin "6") (pinfunction "6_6") (pintype "input"))
    )
    (net (code "61") (name "Net-(BUZZER1-+)") (class "Default")
      (node (ref "BUZZER1") (pin "1") (pinfunction "+_1") (pintype "input"))
      (node (ref "R27") (pin "2") (pinfunction "2_2") (pintype "input"))
    )
    (net (code "62") (name "Net-(BUZZER1--)") (class "Default")
      (node (ref "BUZZER1") (pin "2") (pinfunction "-_2") (pintype "input"))
      (node (ref "Q2") (pin "3") (pinfunction "C_3") (pintype "input"))
    )
    (net (code "63") (name "Net-(C9-Pad2)") (class "Default")
      (node (ref "C9") (pin "2") (pinfunction "2_2") (pintype "input"))
      (node (ref "R4") (pin "1") (pinfunction "1_1") (pintype "input"))
    )
    (net (code "64") (name "Net-(C17-Pad2)") (class "Default")
      (node (ref "C17") (pin "2") (pinfunction "2_2") (pintype "input"))
      (node (ref "R32") (pin "1") (pinfunction "1_1") (pintype "input"))
    )
    (net (code "65") (name "Net-(D1-K)") (class "Default")
      (node (ref "C3") (pin "1") (pinfunction "1_1") (pintype "input"))
      (node (ref "C4") (pin "2") (pinfunction "2_2") (pintype "input"))
      (node (ref "C5") (pin "2") (pinfunction "2_2") (pintype "input"))
      (node (ref "D1") (pin "1") (pinfunction "K_1") (pintype "input"))
      (node (ref "U1") (pin "2") (pinfunction "VIN_2") (pintype "input"))
      (node (ref "U1") (pin "3") (pinfunction "EN_3") (pintype "input"))
    )
    (net (code "66") (name "Net-(H1-Pad1)") (class "Default")
      (node (ref "H1") (pin "1") (pinfunction "1_1") (pintype "input"))
      (node (ref "R14") (pin "2") (pinfunction "2_2") (pintype "input"))
    )
    (net (code "67") (name "Net-(H1-Pad2)") (class "Default")
      (node (ref "H1") (pin "2") (pinfunction "2_2") (pintype "input"))
      (node (ref "R15") (pin "1") (pinfunction "1_1") (pintype "input"))
    )
    (net (code "68") (name "Net-(H1-Pad5)") (class "Default")
      (node (ref "H1") (pin "5") (pinfunction "5_5") (pintype "input"))
      (node (ref "R16") (pin "2") (pinfunction "2_2") (pintype "input"))
    )
    (net (code "69") (name "Net-(H1-Pad6)") (class "Default")
      (node (ref "H1") (pin "6") (pinfunction "6_6") (pintype "input"))
      (node (ref "R17") (pin "1") (pinfunction "1_1") (pintype "input"))
    )
    (net (code "70") (name "Net-(H2-Pad1)") (class "Default")
      (node (ref "H2") (pin "1") (pinfunction "1_1") (pintype "input"))
      (node (ref "R18") (pin "2") (pinfunction "2_2") (pintype "input"))
    )
    (net (code "71") (name "Net-(H2-Pad2)") (class "Default")
      (node (ref "H2") (pin "2") (pinfunction "2_2") (pintype "input"))
      (node (ref "R19") (pin "1") (pinfunction "1_1") (pintype "input"))
    )
    (net (code "72") (name "Net-(H2-Pad5)") (class "Default")
      (node (ref "H2") (pin "5") (pinfunction "5_5") (pintype "input"))
      (node (ref "R20") (pin "2") (pinfunction "2_2") (pintype "input"))
    )
    (net (code "73") (name "Net-(H2-Pad6)") (class "Default")
      (node (ref "H2") (pin "6") (pinfunction "6_6") (pintype "input"))
      (node (ref "R21") (pin "1") (pinfunction "1_1") (pintype "input"))
    )
    (net (code "74") (name "Net-(J3-Pad1)") (class "Default")
      (node (ref "J3") (pin "1") (pinfunction "1_1") (pintype "input"))
      (node (ref "R22") (pin "2") (pinfunction "2_2") (pintype "input"))
    )
    (net (code "75") (name "Net-(J6-+)") (class "Default")
      (node (ref "J6") (pin "1") (pinfunction "+_1") (pintype "input"))
      (node (ref "Q3") (pin "3") (pinfunction "S_3") (pintype "input"))
      (node (ref "S1") (pin "3") (pintype "input"))
      (node (ref "ZD2") (pin "1") (pinfunction "K_1") (pintype "input"))
    )
    (net (code "76") (name "Net-(J10-Pad1)") (class "Default")
      (node (ref "J10") (pin "1") (pinfunction "1_1") (pintype "input"))
      (node (ref "R35") (pin "2") (pinfunction "2_2") (pintype "input"))
    )
    (net (code "77") (name "Net-(J12-Pad1)") (class "Default")
      (node (ref "J12") (pin "1") (pinfunction "1_1") (pintype "input"))
      (node (ref "R42") (pin "2") (pinfunction "2_2") (pintype "input"))
    )
    (net (code "78") (name "Net-(J13-Pad1)") (class "Default")
      (node (ref "J13") (pin "1") (pinfunction "1_1") (pintype "input"))
      (node (ref "R43") (pin "2") (pinfunction "2_2") (pintype "input"))
    )
    (net (code "79") (name "Net-(LED1-Pad1)") (class "Default")
      (node (ref "LED1") (pin "1") (pinfunction "1_1") (pintype "input"))
      (node (ref "R8") (pin "1") (pinfunction "1_1") (pintype "input"))
    )
    (net (code "80") (name "Net-(LED2-Pad1)") (class "Default")
      (node (ref "LED2") (pin "1") (pinfunction "1_1") (pintype "input"))
      (node (ref "R9") (pin "1") (pinfunction "1_1") (pintype "input"))
    )
    (net (code "81") (name "Net-(LED3-Pad1)") (class "Default")
      (node (ref "LED3") (pin "1") (pinfunction "1_1") (pintype "input"))
      (node (ref "R10") (pin "1") (pinfunction "1_1") (pintype "input"))
    )
    (net (code "82") (name "Net-(LED5-Pad1)") (class "Default")
      (node (ref "LED5") (pin "1") (pinfunction "1_1") (pintype "input"))
      (node (ref "R12") (pin "1") (pinfunction "1_1") (pintype "input"))
    )
    (net (code "83") (name "Net-(Q2-B)") (class "Default")
      (node (ref "Q2") (pin "1") (pinfunction "B_1") (pintype "input"))
      (node (ref "R28") (pin "2") (pinfunction "2_2") (pintype "input"))
    )
    (net (code "84") (name "Net-(Q3-G)") (class "Default")
      (node (ref "Q3") (pin "2") (pinfunction "G_2") (pintype "input"))
      (node (ref "S1") (pin "2") (pintype "input"))
    )
    (net (code "85") (name "Net-(R5-Pad2)") (class "Default")
      (node (ref "R5") (pin "2") (pinfunction "2_2") (pintype "input"))
      (node (ref "R6") (pin "1") (pinfunction "1_1") (pintype "input"))
    )
    (net (code "86") (name "Net-(R23-Pad1)") (class "Default")
      (node (ref "R23") (pin "1") (pinfunction "1_1") (pintype "input"))
      (node (ref "U10") (pin "1") (pinfunction "1_1") (pintype "input"))
      (node (ref "U10") (pin "2") (pinfunction "2_2") (pintype "input"))
    )
    (net (code "87") (name "Net-(R24-Pad1)") (class "Default")
      (node (ref "R24") (pin "1") (pinfunction "1_1") (pintype "input"))
      (node (ref "U11") (pin "1") (pinfunction "1_1") (pintype "input"))
      (node (ref "U11") (pin "2") (pinfunction "2_2") (pintype "input"))
    )
    (net (code "88") (name "Net-(R25-Pad1)") (class "Default")
      (node (ref "R25") (pin "1") (pinfunction "1_1") (pintype "input"))
      (node (ref "U12") (pin "1") (pinfunction "1_1") (pintype "input"))
      (node (ref "U12") (pin "2") (pinfunction "2_2") (pintype "input"))
    )
    (net (code "89") (name "Net-(R26-Pad1)") (class "Default")
      (node (ref "R26") (pin "1") (pinfunction "1_1") (pintype "input"))
      (node (ref "U13") (pin "1") (pinfunction "1_1") (pintype "input"))
      (node (ref "U13") (pin "2") (pinfunction "2_2") (pintype "input"))
    )
    (net (code "90") (name "Net-(R31-Pad2)") (class "Default")
      (node (ref "R31") (pin "2") (pinfunction "2_2") (pintype "input"))
      (node (ref "R39") (pin "1") (pinfunction "1_1") (pintype "input"))
      (node (ref "R39") (pin "2") (pinfunction "2_2") (pintype "input"))
    )
    (net (code "91") (name "Net-(R44-Pad2)") (class "Default")
      (node (ref "R44") (pin "2") (pinfunction "2_2") (pintype "input"))
      (node (ref "U17") (pin "7") (pinfunction "7_7") (pintype "unspecified"))
    )
    (net (code "92") (name "Net-(U1-BOOT)") (class "Default")
      (node (ref "C6") (pin "1") (pinfunction "1_1") (pintype "input"))
      (node (ref "U1") (pin "1") (pinfunction "BOOT_1") (pintype "input"))
    )
    (net (code "93") (name "Net-(U1-COMP)") (class "Default")
      (node (ref "R4") (pin "2") (pinfunction "2_2") (pintype "input"))
      (node (ref "U1") (pin "6") (pinfunction "COMP_6") (pintype "input"))
    )
    (net (code "94") (name "Net-(U1-FB)") (class "Default")
      (node (ref "R6") (pin "2") (pinfunction "2_2") (pintype "input"))
      (node (ref "R7") (pin "1") (pinfunction "1_1") (pintype "input"))
      (node (ref "U1") (pin "5") (pinfunction "FB_5") (pintype "input"))
    )
    (net (code "95") (name "Net-(U1-RT{slash}CLK)") (class "Default")
      (node (ref "R3") (pin "2") (pinfunction "2_2") (pintype "input"))
      (node (ref "U1") (pin "4") (pinfunction "RT/CLK_4") (pintype "input"))
    )
    (net (code "96") (name "Net-(U1-SW)") (class "Default")
      (node (ref "C6") (pin "2") (pinfunction "2_2") (pintype "input"))
      (node (ref "L1") (pin "1") (pinfunction "1_1") (pintype "input"))
      (node (ref "U1") (pin "8") (pinfunction "SW_8") (pintype "input"))
    )
    (net (code "97") (name "Net-(U2-CR)") (class "Default")
      (node (ref "R1") (pin "1") (pinfunction "1_1") (pintype "input"))
      (node (ref "R2") (pin "1") (pinfunction "1_1") (pintype "input"))
      (node (ref "U2") (pin "9") (pinfunction "CR_9") (pintype "input"))
    )
    (net (code "98") (name "Net-(U5-SET)") (class "Default")
      (node (ref "R13") (pin "2") (pinfunction "2_2") (pintype "input"))
      (node (ref "U5") (pin "3") (pinfunction "SET_3") (pintype "input"))
    )
    (net (code "99") (name "Net-(U14-BOOT)") (class "Default")
      (node (ref "C19") (pin "1") (pinfunction "1_1") (pintype "input"))
      (node (ref "U14") (pin "1") (pinfunction "BOOT_1") (pintype "input"))
    )
    (net (code "100") (name "Net-(U14-COMP)") (class "Default")
      (node (ref "R32") (pin "2") (pinfunction "2_2") (pintype "input"))
      (node (ref "U14") (pin "6") (pinfunction "COMP_6") (pintype "input"))
    )
    (net (code "101") (name "Net-(U14-FB)") (class "Default")
      (node (ref "R11") (pin "1") (pinfunction "1_1") (pintype "input"))
      (node (ref "R39") (pin "3") (pinfunction "3_3") (pintype "input"))
      (node (ref "U14") (pin "5") (pinfunction "FB_5") (pintype "input"))
    )
    (net (code "102") (name "Net-(U14-RT{slash}CLK)") (class "Default")
      (node (ref "R33") (pin "2") (pinfunction "2_2") (pintype "input"))
      (node (ref "U14") (pin "4") (pinfunction "RT/CLK_4") (pintype "input"))
    )
    (net (code "103") (name "Net-(U14-SW)") (class "Default")
      (node (ref "C19") (pin "2") (pinfunction "2_2") (pintype "input"))
      (node (ref "L2") (pin "1") (pinfunction "1_1") (pintype "input"))
      (node (ref "U14") (pin "8") (pinfunction "SW_8") (pintype "input"))
    )
    (net (code "104") (name "Net-(ZD2-A)") (class "Default")
      (node (ref "R37") (pin "1") (pinfunction "1_1") (pintype "input"))
      (node (ref "S1") (pin "1") (pintype "input"))
      (node (ref "ZD2") (pin "2") (pinfunction "A_2") (pintype "input"))
    )
    (net (code "105") (name "VCCBAT") (class "Default")
      (node (ref "C20") (pin "2") (pinfunction "2_2") (pintype "input"))
      (node (ref "C21") (pin "2") (pinfunction "2_2") (pintype "input"))
      (node (ref "C22") (pin "1") (pinfunction "1_1") (pintype "input"))
      (node (ref "CN1") (pin "2") (pinfunction "2_2") (pintype "input"))
      (node (ref "CN11") (pin "3") (pinfunction "3_3") (pintype "input"))
      (node (ref "CN2") (pin "2") (pinfunction "2_2") (pintype "input"))
      (node (ref "CN3") (pin "3") (pinfunction "3_3") (pintype "input"))
      (node (ref "D1") (pin "2") (pinfunction "A_2") (pintype "input"))
      (node (ref "Q3") (pin "1") (pinfunction "D_1") (pintype "input"))
      (node (ref "U14") (pin "2") (pinfunction "VIN_2") (pintype "input"))
      (node (ref "U14") (pin "3") (pinfunction "EN_3") (pintype "input"))
    )
    (net (code "106") (name "VCC_5V") (class "Default")
      (node (ref "C10") (pin "2") (pinfunction "2_2") (pintype "input"))
      (node (ref "C2") (pin "2") (pinfunction "2_2") (pintype "input"))
      (node (ref "C7") (pin "2") (pinfunction "2_2") (pintype "input"))
      (node (ref "C8") (pin "1") (pinfunction "1_1") (pintype "input"))
      (node (ref "L1") (pin "2") (pinfunction "2_2") (pintype "input"))
      (node (ref "R5") (pin "1") (pinfunction "1_1") (pintype "input"))
      (node (ref "R9") (pin "2") (pinfunction "2_2") (pintype "input"))
      (node (ref "U2") (pin "5") (pinfunction "5V_5") (pintype "input"))
      (node (ref "U2") (pin "6") (pinfunction "5V_6") (pintype "input"))
      (node (ref "U3") (pin "1") (pinfunction "VIN_1") (pintype "input"))
      (node (ref "U5") (pin "5") (pinfunction "IN_5") (pintype "input"))
    )
    (net (code "107") (name "VCC_5V_EXT") (class "Default")
      (node (ref "CN5") (pin "1") (pinfunction "1_1") (pintype "input"))
      (node (ref "CN6") (pin "1") (pinfunction "1_1") (pintype "input"))
      (node (ref "R8") (pin "2") (pinfunction "2_2") (pintype "input"))
      (node (ref "U5") (pin "1") (pinfunction "OUT_1") (pintype "input"))
      (node (ref "U8") (pin "4") (pinfunction "4_4") (pintype "input"))
    )
    (net (code "108") (name "VCC_SERVO") (class "Default")
      (node (ref "C16") (pin "1") (pinfunction "1_1") (pintype "input"))
      (node (ref "C18") (pin "2") (pinfunction "2_2") (pintype "input"))
      (node (ref "J10") (pin "2") (pinfunction "2_2") (pintype "input"))
      (node (ref "J12") (pin "2") (pinfunction "2_2") (pintype "input"))
      (node (ref "J13") (pin "2") (pinfunction "2_2") (pintype "input"))
      (node (ref "J3") (pin "2") (pinfunction "2_2") (pintype "input"))
      (node (ref "L2") (pin "2") (pinfunction "2_2") (pintype "input"))
      (node (ref "R12") (pin "2") (pinfunction "2_2") (pintype "input"))
      (node (ref "R31") (pin "1") (pinfunction "1_1") (pintype "input"))
    )
    (net (code "109") (name "unconnected-(CN8-Pad7)") (class "Default")
      (node (ref "CN8") (pin "7") (pinfunction "7_7") (pintype "input+no_connect"))
    )
    (net (code "110") (name "unconnected-(CN8-Pad8)") (class "Default")
      (node (ref "CN8") (pin "8") (pinfunction "8_8") (pintype "input+no_connect"))
    )
    (net (code "111") (name "unconnected-(H3-Pad5)") (class "Default")
      (node (ref "H3") (pin "5") (pinfunction "5_5") (pintype "input+no_connect"))
    )
    (net (code "112") (name "unconnected-(H3-Pad6)") (class "Default")
      (node (ref "H3") (pin "6") (pinfunction "6_6") (pintype "input+no_connect"))
    )
    (net (code "113") (name "unconnected-(H4-Pad5)") (class "Default")
      (node (ref "H4") (pin "5") (pinfunction "5_5") (pintype "input+no_connect"))
    )
    (net (code "114") (name "unconnected-(H4-Pad6)") (class "Default")
      (node (ref "H4") (pin "6") (pinfunction "6_6") (pintype "input+no_connect"))
    )
    (net (code "115") (name "unconnected-(H5-Pad5)") (class "Default")
      (node (ref "H5") (pin "5") (pinfunction "5_5") (pintype "input+no_connect"))
    )
    (net (code "116") (name "unconnected-(H5-Pad6)") (class "Default")
      (node (ref "H5") (pin "6") (pinfunction "6_6") (pintype "input+no_connect"))
    )
    (net (code "117") (name "unconnected-(H6-Pad5)") (class "Default")
      (node (ref "H6") (pin "5") (pinfunction "5_5") (pintype "input+no_connect"))
    )
    (net (code "118") (name "unconnected-(H6-Pad6)") (class "Default")
      (node (ref "H6") (pin "6") (pinfunction "6_6") (pintype "input+no_connect"))
    )
    (net (code "119") (name "unconnected-(U2-2DN-Pad22)") (class "Default")
      (node (ref "U2") (pin "22") (pinfunction "2DN_22") (pintype "input+no_connect"))
    )
    (net (code "120") (name "unconnected-(U2-2DP-Pad21)") (class "Default")
      (node (ref "U2") (pin "21") (pinfunction "2DP_21") (pintype "input+no_connect"))
    )
    (net (code "121") (name "unconnected-(U2-3V3-Pad3)") (class "Default")
      (node (ref "U2") (pin "3") (pinfunction "3V3_3") (pintype "input+no_connect"))
    )
    (net (code "122") (name "unconnected-(U2-3V3-Pad4)") (class "Default")
      (node (ref "U2") (pin "4") (pinfunction "3V3_4") (pintype "input+no_connect"))
    )
    (net (code "123") (name "unconnected-(U2-B14-Pad30)") (class "Default")
      (node (ref "U2") (pin "30") (pinfunction "B14_30") (pintype "input+no_connect"))
    )
    (net (code "124") (name "unconnected-(U2-B15-Pad28)") (class "Default")
      (node (ref "U2") (pin "28") (pinfunction "B15_28") (pintype "input+no_connect"))
    )
    (net (code "125") (name "unconnected-(U2-B16-Pad32)") (class "Default")
      (node (ref "U2") (pin "32") (pinfunction "B16_32") (pintype "input+no_connect"))
    )
    (net (code "126") (name "unconnected-(U2-B17-Pad31)") (class "Default")
      (node (ref "U2") (pin "31") (pinfunction "B17_31") (pintype "input+no_connect"))
    )
    (net (code "127") (name "unconnected-(U2-B21-Pad35)") (class "Default")
      (node (ref "U2") (pin "35") (pinfunction "B21_35") (pintype "input+no_connect"))
    )
    (net (code "128") (name "unconnected-(U2-B23-Pad37)") (class "Default")
      (node (ref "U2") (pin "37") (pinfunction "B23_37") (pintype "input+no_connect"))
    )
    (net (code "129") (name "unconnected-(U2-C9-Pad71)") (class "Default")
      (node (ref "U2") (pin "71") (pinfunction "C9_71") (pintype "input+no_connect"))
    )
    (net (code "130") (name "unconnected-(U2-C10-Pad72)") (class "Default")
      (node (ref "U2") (pin "72") (pinfunction "C10_72") (pintype "input+no_connect"))
    )
    (net (code "131") (name "unconnected-(U2-C11-Pad69)") (class "Default")
      (node (ref "U2") (pin "69") (pinfunction "C11_69") (pintype "input+no_connect"))
    )
    (net (code "132") (name "unconnected-(U2-C12-Pad70)") (class "Default")
      (node (ref "U2") (pin "70") (pinfunction "C12_70") (pintype "input+no_connect"))
    )
    (net (code "133") (name "unconnected-(U2-C13-Pad67)") (class "Default")
      (node (ref "U2") (pin "67") (pinfunction "C13_67") (pintype "input+no_connect"))
    )
    (net (code "134") (name "unconnected-(U2-C14-Pad68)") (class "Default")
      (node (ref "U2") (pin "68") (pinfunction "C14_68") (pintype "input+no_connect"))
    )
    (net (code "135") (name "unconnected-(U2-C15-Pad65)") (class "Default")
      (node (ref "U2") (pin "65") (pinfunction "C15_65") (pintype "input+no_connect"))
    )
    (net (code "136") (name "unconnected-(U2-D4-Pad10)") (class "Default")
      (node (ref "U2") (pin "10") (pinfunction "D4_10") (pintype "input+no_connect"))
    )
    (net (code "137") (name "unconnected-(U2-D27-Pad81)") (class "Default")
      (node (ref "U2") (pin "81") (pinfunction "D27_81") (pintype "input+no_connect"))
    )
    (net (code "138") (name "unconnected-(U2-OF-Pad7)") (class "Default")
      (node (ref "U2") (pin "7") (pinfunction "OF_7") (pintype "input+no_connect"))
    )
    (net (code "139") (name "unconnected-(U2-WU-Pad8)") (class "Default")
      (node (ref "U2") (pin "8") (pinfunction "WU_8") (pintype "input+no_connect"))
    )
    (net (code "140") (name "unconnected-(U3-NC-Pad4)") (class "Default")
      (node (ref "U3") (pin "4") (pinfunction "NC_4") (pintype "input+no_connect"))
    )
    (net (code "141") (name "unconnected-(U8-Pad5)") (class "Default")
      (node (ref "U8") (pin "5") (pinfunction "5_5") (pintype "input+no_connect"))
    )
    (net (code "142") (name "unconnected-(U8-Pad8)") (class "Default")
      (node (ref "U8") (pin "8") (pinfunction "8_8") (pintype "input+no_connect"))
    )
  )
)
